# MCP960XL-L0X-RL0X_EVM_v1.net
KiCad netlist of a schematic drawn in EAGLE
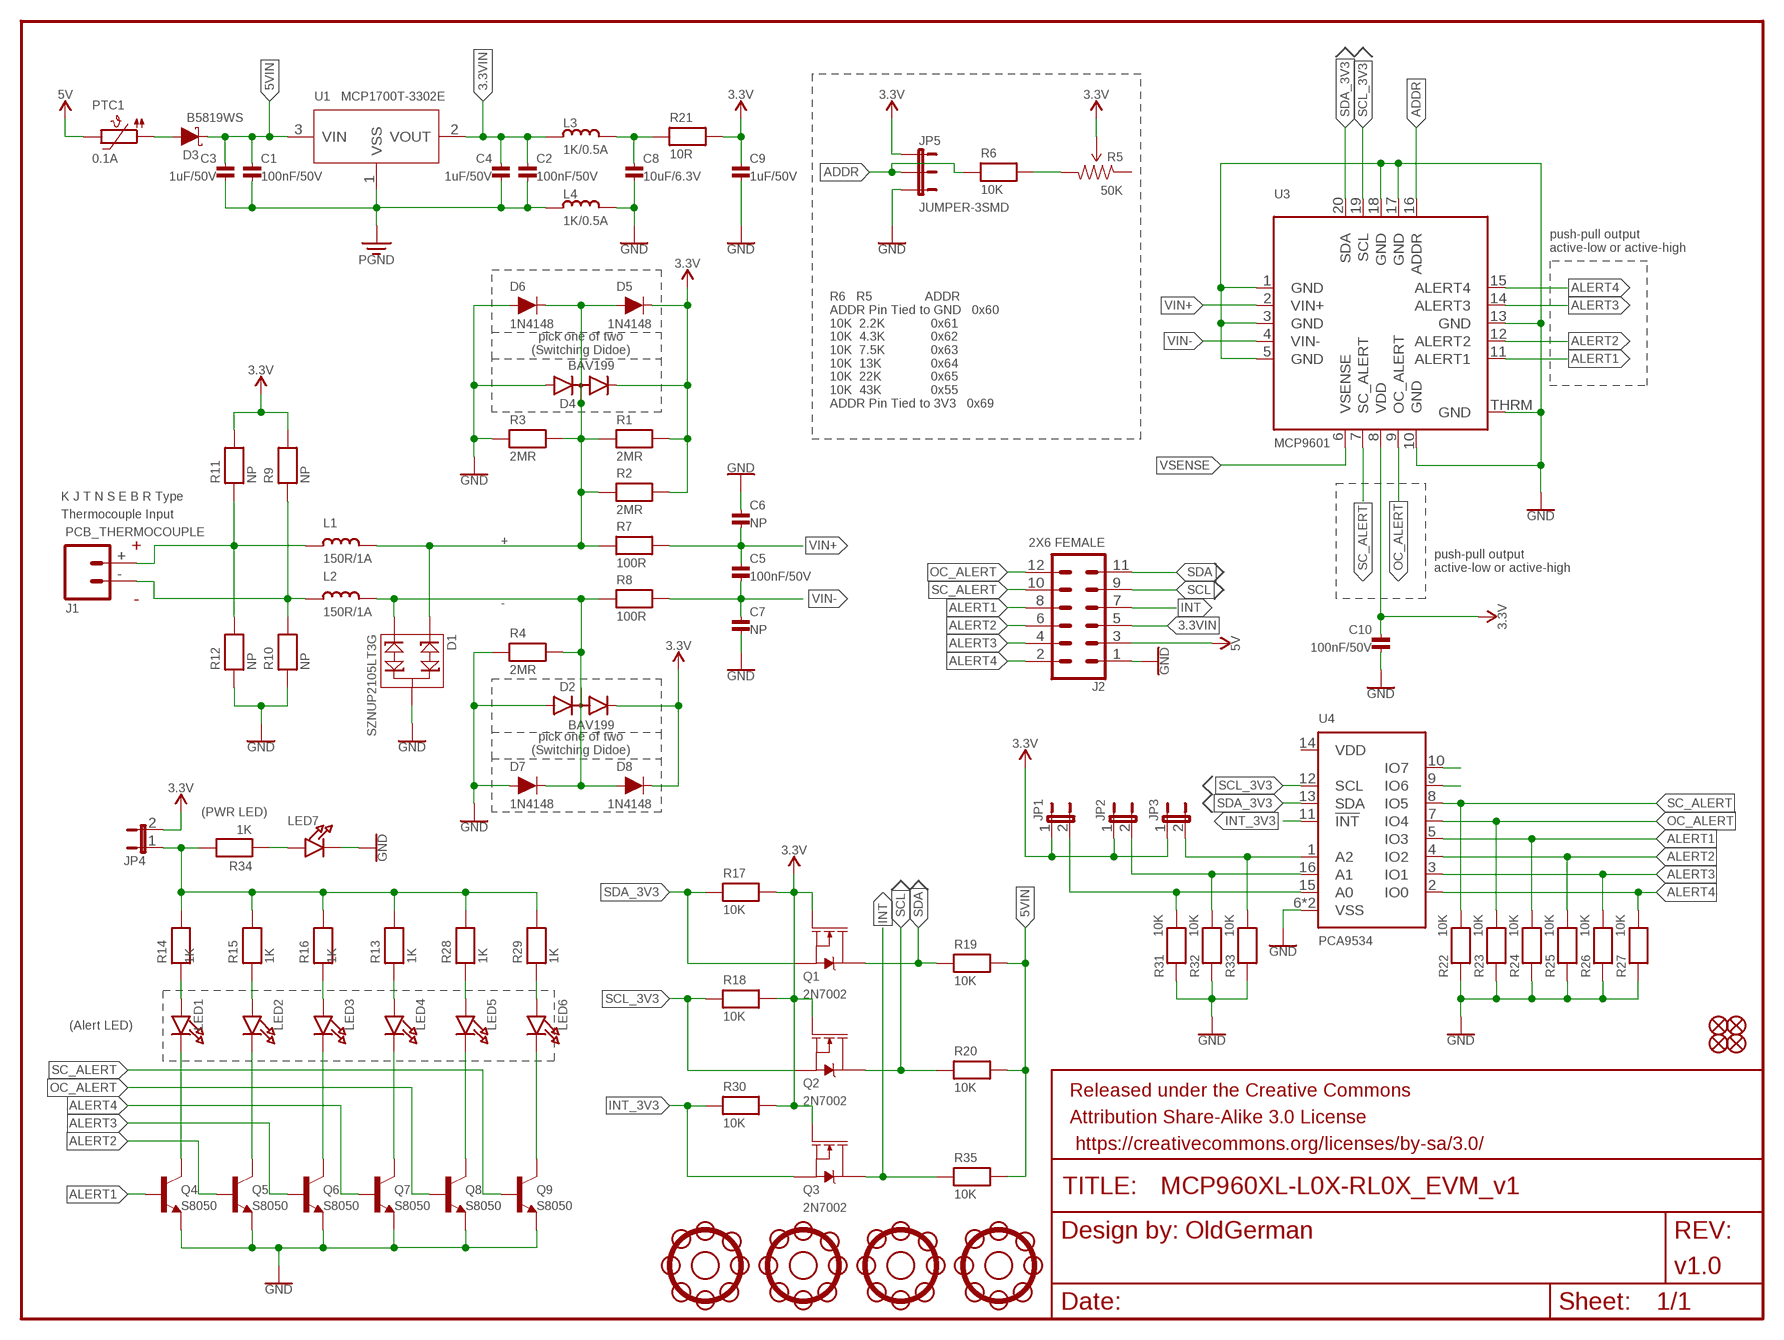
[diagram p0: schematic, sheet 1]

(export (version "E")
  (design (tool "Eeschema 10.0.6"))
  (components
    (comp (ref "C1")
      (value "100nF/50V")
      (footprint "eagle-import:0603")
      (libsource (lib "eagle-import") (part "CAP_CERAMIC0603"))
    )
    (comp (ref "C2")
      (value "100nF/50V")
      (footprint "eagle-import:0603")
      (libsource (lib "eagle-import") (part "CAP_CERAMIC0603"))
    )
    (comp (ref "C3")
      (value "1uF/50V")
      (footprint "eagle-import:0603")
      (libsource (lib "eagle-import") (part "CAP_CERAMIC0603"))
    )
    (comp (ref "C4")
      (value "1uF/50V")
      (footprint "eagle-import:0603")
      (libsource (lib "eagle-import") (part "CAP_CERAMIC0603"))
    )
    (comp (ref "C5")
      (value "100nF/50V")
      (footprint "eagle-import:0603")
      (libsource (lib "eagle-import") (part "CAP_CERAMIC0603"))
    )
    (comp (ref "C6")
      (value "NP")
      (footprint "eagle-import:0603")
      (libsource (lib "eagle-import") (part "CAP_CERAMIC0603"))
    )
    (comp (ref "C7")
      (value "NP")
      (footprint "eagle-import:0603")
      (libsource (lib "eagle-import") (part "CAP_CERAMIC0603"))
    )
    (comp (ref "C8")
      (value "10uF/6.3V")
      (footprint "eagle-import:0603")
      (libsource (lib "eagle-import") (part "CAP_CERAMIC0603"))
    )
    (comp (ref "C9")
      (value "1uF/50V")
      (footprint "eagle-import:0603")
      (libsource (lib "eagle-import") (part "CAP_CERAMIC0603"))
    )
    (comp (ref "C10")
      (value "100nF/50V")
      (footprint "eagle-import:0603")
      (libsource (lib "eagle-import") (part "CAP_CERAMIC0603"))
    )
    (comp (ref "D1")
      (value "SZNUP2105LT3G")
      (footprint "eagle-import:SOT23-3")
      (libsource (lib "eagle-import") (part "SZNUP2105LT3G"))
    )
    (comp (ref "D2")
      (value "BAV199")
      (footprint "eagle-import:SOT23-3")
      (libsource (lib "eagle-import") (part "BAV199"))
    )
    (comp (ref "D3")
      (value "B5819WS")
      (footprint "eagle-import:SOD-323")
      (libsource (lib "eagle-import") (part "DIODE_SCHOTTKYSOD323"))
    )
    (comp (ref "D4")
      (value "BAV199")
      (footprint "eagle-import:SOT23-3")
      (libsource (lib "eagle-import") (part "BAV199"))
    )
    (comp (ref "D5")
      (value "1N4148")
      (footprint "eagle-import:SOD-323")
      (libsource (lib "eagle-import") (part "DIODE"))
    )
    (comp (ref "D6")
      (value "1N4148")
      (footprint "eagle-import:SOD-323")
      (libsource (lib "eagle-import") (part "DIODE"))
    )
    (comp (ref "D7")
      (value "1N4148")
      (footprint "eagle-import:SOD-323")
      (libsource (lib "eagle-import") (part "DIODE"))
    )
    (comp (ref "D8")
      (value "1N4148")
      (footprint "eagle-import:SOD-323")
      (libsource (lib "eagle-import") (part "DIODE"))
    )
    (comp (ref "FID1")
      (value "FIDUCIAL1X2.5")
      (footprint "eagle-import:FIDUCIAL-1X2.5")
      (libsource (lib "eagle-import") (part "FIDUCIAL1X2.5"))
    )
    (comp (ref "FID2")
      (value "FIDUCIAL1X2.5")
      (footprint "eagle-import:FIDUCIAL-1X2.5")
      (libsource (lib "eagle-import") (part "FIDUCIAL1X2.5"))
    )
    (comp (ref "FID3")
      (value "FIDUCIAL1X2.5")
      (footprint "eagle-import:FIDUCIAL-1X2.5")
      (libsource (lib "eagle-import") (part "FIDUCIAL1X2.5"))
    )
    (comp (ref "FID4")
      (value "FIDUCIAL1X2.5")
      (footprint "eagle-import:FIDUCIAL-1X2.5")
      (libsource (lib "eagle-import") (part "FIDUCIAL1X2.5"))
    )
    (comp (ref "FRAME1")
      (value "FRAME-LETTER")
      (footprint "eagle-import:CREATIVE_COMMONS")
      (libsource (lib "eagle-import") (part "FRAME-LETTER"))
    )
    (comp (ref "J1")
      (value "PCB_THERMOCOUPLE")
      (footprint "eagle-import:PCC-SMP")
      (libsource (lib "eagle-import") (part "PCB_THERMOCOUPLE"))
    )
    (comp (ref "J2")
      (value "2X6 FEMALE")
      (footprint "eagle-import:2X6")
      (libsource (lib "eagle-import") (part "CONN_06X2PTH_FEMALE"))
    )
    (comp (ref "JP1")
      (value "JUMPER-2SMD-NC")
      (footprint "eagle-import:SJ_2S")
      (libsource (lib "eagle-import") (part "JUMPER-2SMD-NC"))
    )
    (comp (ref "JP2")
      (value "JUMPER-2SMD-NC")
      (footprint "eagle-import:SJ_2S")
      (libsource (lib "eagle-import") (part "JUMPER-2SMD-NC"))
    )
    (comp (ref "JP3")
      (value "JUMPER-2SMD-NC")
      (footprint "eagle-import:SJ_2S")
      (libsource (lib "eagle-import") (part "JUMPER-2SMD-NC"))
    )
    (comp (ref "JP4")
      (value "JUMPER-2SMD-NC")
      (footprint "eagle-import:SJ_2S")
      (libsource (lib "eagle-import") (part "JUMPER-2SMD-NC"))
    )
    (comp (ref "JP5")
      (value "JUMPER-3SMD")
      (footprint "eagle-import:SJ_3")
      (libsource (lib "eagle-import") (part "JUMPER-3SMD"))
    )
    (comp (ref "L1")
      (value "150R/1A")
      (footprint "eagle-import:0603")
      (libsource (lib "eagle-import") (part "INDUCTOR0603"))
    )
    (comp (ref "L2")
      (value "150R/1A")
      (footprint "eagle-import:0603")
      (libsource (lib "eagle-import") (part "INDUCTOR0603"))
    )
    (comp (ref "L3")
      (value "1K/0.5A")
      (footprint "eagle-import:0603")
      (libsource (lib "eagle-import") (part "INDUCTOR0603"))
    )
    (comp (ref "L4")
      (value "1K/0.5A")
      (footprint "eagle-import:0603")
      (libsource (lib "eagle-import") (part "INDUCTOR0603"))
    )
    (comp (ref "LED1")
      (value "LED0603")
      (footprint "eagle-import:CHIPLED_0603")
      (libsource (lib "eagle-import") (part "LED0603"))
    )
    (comp (ref "LED2")
      (value "LED0603")
      (footprint "eagle-import:CHIPLED_0603")
      (libsource (lib "eagle-import") (part "LED0603"))
    )
    (comp (ref "LED3")
      (value "LED0603")
      (footprint "eagle-import:CHIPLED_0603")
      (libsource (lib "eagle-import") (part "LED0603"))
    )
    (comp (ref "LED4")
      (value "LED0603")
      (footprint "eagle-import:CHIPLED_0603")
      (libsource (lib "eagle-import") (part "LED0603"))
    )
    (comp (ref "LED5")
      (value "LED0603")
      (footprint "eagle-import:CHIPLED_0603")
      (libsource (lib "eagle-import") (part "LED0603"))
    )
    (comp (ref "LED6")
      (value "LED0603")
      (footprint "eagle-import:CHIPLED_0603")
      (libsource (lib "eagle-import") (part "LED0603"))
    )
    (comp (ref "LED7")
      (value "LED0603")
      (footprint "eagle-import:CHIPLED_0603")
      (libsource (lib "eagle-import") (part "LED0603"))
    )
    (comp (ref "PTC1")
      (value "0.1A")
      (footprint "eagle-import:1206")
      (libsource (lib "eagle-import") (part "PTC1206"))
    )
    (comp (ref "Q1")
      (value "2N7002")
      (footprint "eagle-import:SOT23-3")
      (libsource (lib "eagle-import") (part "MOSFET-NCH-AO3404A"))
    )
    (comp (ref "Q2")
      (value "2N7002")
      (footprint "eagle-import:SOT23-3")
      (libsource (lib "eagle-import") (part "MOSFET-NCH-AO3404A"))
    )
    (comp (ref "Q3")
      (value "2N7002")
      (footprint "eagle-import:SOT23-3")
      (libsource (lib "eagle-import") (part "MOSFET-NCH-AO3404A"))
    )
    (comp (ref "Q4")
      (value "S8050")
      (footprint "eagle-import:SOT23-3")
      (libsource (lib "eagle-import") (part "TRANS_NPN-MMBT2222AL"))
    )
    (comp (ref "Q5")
      (value "S8050")
      (footprint "eagle-import:SOT23-3")
      (libsource (lib "eagle-import") (part "TRANS_NPN-MMBT2222AL"))
    )
    (comp (ref "Q6")
      (value "S8050")
      (footprint "eagle-import:SOT23-3")
      (libsource (lib "eagle-import") (part "TRANS_NPN-MMBT2222AL"))
    )
    (comp (ref "Q7")
      (value "S8050")
      (footprint "eagle-import:SOT23-3")
      (libsource (lib "eagle-import") (part "TRANS_NPN-MMBT2222AL"))
    )
    (comp (ref "Q8")
      (value "S8050")
      (footprint "eagle-import:SOT23-3")
      (libsource (lib "eagle-import") (part "TRANS_NPN-MMBT2222AL"))
    )
    (comp (ref "Q9")
      (value "S8050")
      (footprint "eagle-import:SOT23-3")
      (libsource (lib "eagle-import") (part "TRANS_NPN-MMBT2222AL"))
    )
    (comp (ref "R1")
      (value "2MR")
      (footprint "eagle-import:0603")
      (libsource (lib "eagle-import") (part "RESISTOR0603"))
    )
    (comp (ref "R2")
      (value "2MR")
      (footprint "eagle-import:0603")
      (libsource (lib "eagle-import") (part "RESISTOR0603"))
    )
    (comp (ref "R3")
      (value "2MR")
      (footprint "eagle-import:0603")
      (libsource (lib "eagle-import") (part "RESISTOR0603"))
    )
    (comp (ref "R4")
      (value "2MR")
      (footprint "eagle-import:0603")
      (libsource (lib "eagle-import") (part "RESISTOR0603"))
    )
    (comp (ref "R5")
      (value "50K")
      (footprint "eagle-import:TRIMPOT-3MM")
      (libsource (lib "eagle-import") (part "POT-SMD"))
    )
    (comp (ref "R6")
      (value "10K")
      (footprint "eagle-import:0603")
      (libsource (lib "eagle-import") (part "RESISTOR0603"))
    )
    (comp (ref "R7")
      (value "100R")
      (footprint "eagle-import:0603")
      (libsource (lib "eagle-import") (part "RESISTOR0603"))
    )
    (comp (ref "R8")
      (value "100R")
      (footprint "eagle-import:0603")
      (libsource (lib "eagle-import") (part "RESISTOR0603"))
    )
    (comp (ref "R9")
      (value "NP")
      (footprint "eagle-import:0603")
      (libsource (lib "eagle-import") (part "RESISTOR0603"))
    )
    (comp (ref "R10")
      (value "NP")
      (footprint "eagle-import:0603")
      (libsource (lib "eagle-import") (part "RESISTOR0603"))
    )
    (comp (ref "R11")
      (value "NP")
      (footprint "eagle-import:0603")
      (libsource (lib "eagle-import") (part "RESISTOR0603"))
    )
    (comp (ref "R12")
      (value "NP")
      (footprint "eagle-import:0603")
      (libsource (lib "eagle-import") (part "RESISTOR0603"))
    )
    (comp (ref "R13")
      (value "1K")
      (footprint "eagle-import:0603")
      (libsource (lib "eagle-import") (part "RESISTOR0603"))
    )
    (comp (ref "R14")
      (value "1K")
      (footprint "eagle-import:0603")
      (libsource (lib "eagle-import") (part "RESISTOR0603"))
    )
    (comp (ref "R15")
      (value "1K")
      (footprint "eagle-import:0603")
      (libsource (lib "eagle-import") (part "RESISTOR0603"))
    )
    (comp (ref "R16")
      (value "1K")
      (footprint "eagle-import:0603")
      (libsource (lib "eagle-import") (part "RESISTOR0603"))
    )
    (comp (ref "R17")
      (value "10K")
      (footprint "eagle-import:0603")
      (libsource (lib "eagle-import") (part "RESISTOR0603"))
    )
    (comp (ref "R18")
      (value "10K")
      (footprint "eagle-import:0603")
      (libsource (lib "eagle-import") (part "RESISTOR0603"))
    )
    (comp (ref "R19")
      (value "10K")
      (footprint "eagle-import:0603")
      (libsource (lib "eagle-import") (part "RESISTOR0603"))
    )
    (comp (ref "R20")
      (value "10K")
      (footprint "eagle-import:0603")
      (libsource (lib "eagle-import") (part "RESISTOR0603"))
    )
    (comp (ref "R21")
      (value "10R")
      (footprint "eagle-import:0603")
      (libsource (lib "eagle-import") (part "RESISTOR0603"))
    )
    (comp (ref "R22")
      (value "10K")
      (footprint "eagle-import:0603")
      (libsource (lib "eagle-import") (part "RESISTOR0603"))
    )
    (comp (ref "R23")
      (value "10K")
      (footprint "eagle-import:0603")
      (libsource (lib "eagle-import") (part "RESISTOR0603"))
    )
    (comp (ref "R24")
      (value "10K")
      (footprint "eagle-import:0603")
      (libsource (lib "eagle-import") (part "RESISTOR0603"))
    )
    (comp (ref "R25")
      (value "10K")
      (footprint "eagle-import:0603")
      (libsource (lib "eagle-import") (part "RESISTOR0603"))
    )
    (comp (ref "R26")
      (value "10K")
      (footprint "eagle-import:0603")
      (libsource (lib "eagle-import") (part "RESISTOR0603"))
    )
    (comp (ref "R27")
      (value "10K")
      (footprint "eagle-import:0603")
      (libsource (lib "eagle-import") (part "RESISTOR0603"))
    )
    (comp (ref "R28")
      (value "1K")
      (footprint "eagle-import:0603")
      (libsource (lib "eagle-import") (part "RESISTOR0603"))
    )
    (comp (ref "R29")
      (value "1K")
      (footprint "eagle-import:0603")
      (libsource (lib "eagle-import") (part "RESISTOR0603"))
    )
    (comp (ref "R30")
      (value "10K")
      (footprint "eagle-import:0603")
      (libsource (lib "eagle-import") (part "RESISTOR0603"))
    )
    (comp (ref "R31")
      (value "10K")
      (footprint "eagle-import:0603")
      (libsource (lib "eagle-import") (part "RESISTOR0603"))
    )
    (comp (ref "R32")
      (value "10K")
      (footprint "eagle-import:0603")
      (libsource (lib "eagle-import") (part "RESISTOR0603"))
    )
    (comp (ref "R33")
      (value "10K")
      (footprint "eagle-import:0603")
      (libsource (lib "eagle-import") (part "RESISTOR0603"))
    )
    (comp (ref "R34")
      (value "1K")
      (footprint "eagle-import:0603")
      (libsource (lib "eagle-import") (part "RESISTOR0603"))
    )
    (comp (ref "R35")
      (value "10K")
      (footprint "eagle-import:0603")
      (libsource (lib "eagle-import") (part "RESISTOR0603"))
    )
    (comp (ref "U$1")
      (value "SUN_HOLE_M3")
      (footprint "eagle-import:SUN_HOLE_M3")
      (libsource (lib "eagle-import") (part "SUN_HOLE_M3"))
    )
    (comp (ref "U$3")
      (value "SUN_HOLE_M3")
      (footprint "eagle-import:SUN_HOLE_M3")
      (libsource (lib "eagle-import") (part "SUN_HOLE_M3"))
    )
    (comp (ref "U$4")
      (value "SUN_HOLE_M3")
      (footprint "eagle-import:SUN_HOLE_M3")
      (libsource (lib "eagle-import") (part "SUN_HOLE_M3"))
    )
    (comp (ref "U$6")
      (value "SUN_HOLE_M3")
      (footprint "eagle-import:SUN_HOLE_M3")
      (libsource (lib "eagle-import") (part "SUN_HOLE_M3"))
    )
    (comp (ref "U1")
      (value "MCP1700T-3302E")
      (footprint "eagle-import:SOT23-3")
      (libsource (lib "eagle-import") (part "LDO_3PIN"))
    )
    (comp (ref "U3")
      (value "MCP9601")
      (footprint "eagle-import:VQFN20_5MM")
      (libsource (lib "eagle-import") (part "MCP9601"))
    )
    (comp (ref "U4")
      (value "PCA9534")
      (footprint "eagle-import:HVQFN16_4X4_0.65MM")
      (libsource (lib "eagle-import") (part "PCA9534"))
    )
  )
  (nets
    (net (code "1") (name "/VDD") (class "Default")
      (node (ref "U4") (pin "14") (pinfunction "VDD_14") (pintype "power_in"))
    )
    (net (code "2") (name "3.3V") (class "Default")
      (node (ref "C10") (pin "1") (pinfunction "P$1_1") (pintype "passive"))
      (node (ref "C9") (pin "1") (pinfunction "P$1_1") (pintype "passive"))
      (node (ref "D2") (pin "3") (pinfunction "C_3") (pintype "passive"))
      (node (ref "D4") (pin "3") (pinfunction "C_3") (pintype "passive"))
      (node (ref "D5") (pin "C") (pinfunction "C_C") (pintype "passive"))
      (node (ref "D8") (pin "C") (pinfunction "C_C") (pintype "passive"))
      (node (ref "JP1") (pin "1") (pinfunction "1_1") (pintype "passive"))
      (node (ref "JP2") (pin "1") (pinfunction "1_1") (pintype "passive"))
      (node (ref "JP3") (pin "1") (pinfunction "1_1") (pintype "passive"))
      (node (ref "JP4") (pin "2") (pinfunction "2_2") (pintype "passive"))
      (node (ref "JP5") (pin "1") (pinfunction "1_1") (pintype "passive"))
      (node (ref "Q1") (pin "1") (pinfunction "G_1") (pintype "bidirectional"))
      (node (ref "Q2") (pin "1") (pinfunction "G_1") (pintype "bidirectional"))
      (node (ref "Q3") (pin "1") (pinfunction "G_1") (pintype "bidirectional"))
      (node (ref "R1") (pin "2") (pinfunction "2_2") (pintype "passive"))
      (node (ref "R11") (pin "2") (pinfunction "2_2") (pintype "passive"))
      (node (ref "R17") (pin "2") (pinfunction "2_2") (pintype "passive"))
      (node (ref "R18") (pin "2") (pinfunction "2_2") (pintype "passive"))
      (node (ref "R2") (pin "2") (pinfunction "2_2") (pintype "passive"))
      (node (ref "R21") (pin "2") (pinfunction "2_2") (pintype "passive"))
      (node (ref "R30") (pin "2") (pinfunction "2_2") (pintype "passive"))
      (node (ref "R5") (pin "2") (pinfunction "WIPER_2") (pintype "passive"))
      (node (ref "R9") (pin "2") (pinfunction "2_2") (pintype "passive"))
      (node (ref "U3") (pin "8") (pinfunction "VDD_8") (pintype "bidirectional"))
    )
    (net (code "3") (name "3.3VIN") (class "Default")
      (node (ref "C2") (pin "1") (pinfunction "P$1_1") (pintype "passive"))
      (node (ref "C4") (pin "1") (pinfunction "P$1_1") (pintype "passive"))
      (node (ref "J2") (pin "5") (pinfunction "5_5") (pintype "passive"))
      (node (ref "L3") (pin "1") (pinfunction "1_1") (pintype "passive"))
      (node (ref "U1") (pin "2") (pinfunction "VOUT_2") (pintype "bidirectional"))
    )
    (net (code "4") (name "5V") (class "Default")
      (node (ref "J2") (pin "3") (pinfunction "3_3") (pintype "passive"))
      (node (ref "PTC1") (pin "2") (pinfunction "2_2") (pintype "passive"))
    )
    (net (code "5") (name "5VIN") (class "Default")
      (node (ref "C1") (pin "1") (pinfunction "P$1_1") (pintype "passive"))
      (node (ref "C3") (pin "1") (pinfunction "P$1_1") (pintype "passive"))
      (node (ref "D3") (pin "C") (pinfunction "C_C") (pintype "passive"))
      (node (ref "R19") (pin "2") (pinfunction "2_2") (pintype "passive"))
      (node (ref "R20") (pin "2") (pinfunction "2_2") (pintype "passive"))
      (node (ref "R35") (pin "2") (pinfunction "2_2") (pintype "passive"))
      (node (ref "U1") (pin "3") (pinfunction "VIN_3") (pintype "bidirectional"))
    )
    (net (code "6") (name "ADDR") (class "Default")
      (node (ref "JP5") (pin "2") (pinfunction "2_2") (pintype "passive"))
      (node (ref "R6") (pin "1") (pinfunction "1_1") (pintype "passive"))
      (node (ref "U3") (pin "16") (pinfunction "ADDR_16") (pintype "bidirectional"))
    )
    (net (code "7") (name "ALERT1") (class "Default")
      (node (ref "J2") (pin "8") (pinfunction "8_8") (pintype "passive"))
      (node (ref "Q4") (pin "1") (pinfunction "B_1") (pintype "passive"))
      (node (ref "R24") (pin "2") (pinfunction "2_2") (pintype "passive"))
      (node (ref "U3") (pin "11") (pinfunction "ALERT1_11") (pintype "bidirectional"))
      (node (ref "U4") (pin "5") (pinfunction "IO3_5") (pintype "bidirectional"))
    )
    (net (code "8") (name "ALERT2") (class "Default")
      (node (ref "J2") (pin "6") (pinfunction "6_6") (pintype "passive"))
      (node (ref "Q5") (pin "1") (pinfunction "B_1") (pintype "passive"))
      (node (ref "R25") (pin "2") (pinfunction "2_2") (pintype "passive"))
      (node (ref "U3") (pin "12") (pinfunction "ALERT2_12") (pintype "bidirectional"))
      (node (ref "U4") (pin "4") (pinfunction "IO2_4") (pintype "bidirectional"))
    )
    (net (code "9") (name "ALERT3") (class "Default")
      (node (ref "J2") (pin "4") (pinfunction "4_4") (pintype "passive"))
      (node (ref "Q6") (pin "1") (pinfunction "B_1") (pintype "passive"))
      (node (ref "R26") (pin "2") (pinfunction "2_2") (pintype "passive"))
      (node (ref "U3") (pin "14") (pinfunction "ALERT3_14") (pintype "bidirectional"))
      (node (ref "U4") (pin "3") (pinfunction "IO1_3") (pintype "bidirectional"))
    )
    (net (code "10") (name "ALERT4") (class "Default")
      (node (ref "J2") (pin "2") (pinfunction "2_2") (pintype "passive"))
      (node (ref "Q7") (pin "1") (pinfunction "B_1") (pintype "passive"))
      (node (ref "R27") (pin "2") (pinfunction "2_2") (pintype "passive"))
      (node (ref "U3") (pin "15") (pinfunction "ALERT4_15") (pintype "bidirectional"))
      (node (ref "U4") (pin "2") (pinfunction "IO0_2") (pintype "bidirectional"))
    )
    (net (code "11") (name "GND") (class "Default")
      (node (ref "C10") (pin "2") (pinfunction "P$2_2") (pintype "passive"))
      (node (ref "C6") (pin "1") (pinfunction "P$1_1") (pintype "passive"))
      (node (ref "C7") (pin "2") (pinfunction "P$2_2") (pintype "passive"))
      (node (ref "C8") (pin "2") (pinfunction "P$2_2") (pintype "passive"))
      (node (ref "C9") (pin "2") (pinfunction "P$2_2") (pintype "passive"))
      (node (ref "D1") (pin "3") (pinfunction "3_3") (pintype "bidirectional"))
      (node (ref "D2") (pin "1") (pinfunction "A_1") (pintype "passive"))
      (node (ref "D4") (pin "1") (pinfunction "A_1") (pintype "passive"))
      (node (ref "D6") (pin "A") (pinfunction "A_A") (pintype "passive"))
      (node (ref "D7") (pin "A") (pinfunction "A_A") (pintype "passive"))
      (node (ref "J2") (pin "1") (pinfunction "1_1") (pintype "passive"))
      (node (ref "JP5") (pin "3") (pinfunction "3_3") (pintype "passive"))
      (node (ref "L4") (pin "2") (pinfunction "2_2") (pintype "passive"))
      (node (ref "LED7") (pin "C") (pinfunction "C_C") (pintype "passive"))
      (node (ref "Q4") (pin "2") (pinfunction "E_2") (pintype "passive"))
      (node (ref "Q5") (pin "2") (pinfunction "E_2") (pintype "passive"))
      (node (ref "Q6") (pin "2") (pinfunction "E_2") (pintype "passive"))
      (node (ref "Q7") (pin "2") (pinfunction "E_2") (pintype "passive"))
      (node (ref "Q8") (pin "2") (pinfunction "E_2") (pintype "passive"))
      (node (ref "Q9") (pin "2") (pinfunction "E_2") (pintype "passive"))
      (node (ref "R10") (pin "1") (pinfunction "1_1") (pintype "passive"))
      (node (ref "R12") (pin "1") (pinfunction "1_1") (pintype "passive"))
      (node (ref "R22") (pin "1") (pinfunction "1_1") (pintype "passive"))
      (node (ref "R23") (pin "1") (pinfunction "1_1") (pintype "passive"))
      (node (ref "R24") (pin "1") (pinfunction "1_1") (pintype "passive"))
      (node (ref "R25") (pin "1") (pinfunction "1_1") (pintype "passive"))
      (node (ref "R26") (pin "1") (pinfunction "1_1") (pintype "passive"))
      (node (ref "R27") (pin "1") (pinfunction "1_1") (pintype "passive"))
      (node (ref "R3") (pin "1") (pinfunction "1_1") (pintype "passive"))
      (node (ref "R31") (pin "1") (pinfunction "1_1") (pintype "passive"))
      (node (ref "R32") (pin "1") (pinfunction "1_1") (pintype "passive"))
      (node (ref "R33") (pin "1") (pinfunction "1_1") (pintype "passive"))
      (node (ref "R4") (pin "1") (pinfunction "1_1") (pintype "passive"))
      (node (ref "U3") (pin "1") (pinfunction "GND_1") (pintype "bidirectional"))
      (node (ref "U3") (pin "10") (pinfunction "GND_10") (pintype "bidirectional"))
      (node (ref "U3") (pin "13") (pinfunction "GND_13") (pintype "bidirectional"))
      (node (ref "U3") (pin "17") (pinfunction "GND_17") (pintype "bidirectional"))
      (node (ref "U3") (pin "18") (pinfunction "GND_18") (pintype "bidirectional"))
      (node (ref "U3") (pin "3") (pinfunction "GND_3") (pintype "bidirectional"))
      (node (ref "U3") (pin "5") (pinfunction "GND_5") (pintype "bidirectional"))
      (node (ref "U3") (pin "THRM") (pinfunction "GND_THRM") (pintype "bidirectional"))
      (node (ref "U4") (pin "6") (pinfunction "VSS_6") (pintype "power_in"))
      (node (ref "U4") (pin "PAD") (pinfunction "VSS_PAD") (pintype "power_in"))
    )
    (net (code "12") (name "INT") (class "Default")
      (node (ref "J2") (pin "7") (pinfunction "7_7") (pintype "passive"))
      (node (ref "Q3") (pin "3") (pinfunction "D_3") (pintype "bidirectional"))
      (node (ref "R35") (pin "1") (pinfunction "1_1") (pintype "passive"))
    )
    (net (code "13") (name "INT_3V3") (class "Default")
      (node (ref "Q3") (pin "2") (pinfunction "S_2") (pintype "bidirectional"))
      (node (ref "R30") (pin "1") (pinfunction "1_1") (pintype "passive"))
      (node (ref "U4") (pin "11") (pinfunction "~{INT}_11") (pintype "open_collector"))
    )
    (net (code "14") (name "Net-(C8-P$1)") (class "Default")
      (node (ref "C8") (pin "1") (pinfunction "P$1_1") (pintype "passive"))
      (node (ref "L3") (pin "2") (pinfunction "2_2") (pintype "passive"))
      (node (ref "R21") (pin "1") (pinfunction "1_1") (pintype "passive"))
    )
    (net (code "15") (name "Net-(D2-AC)") (class "Default")
      (node (ref "D1") (pin "2") (pinfunction "2_2") (pintype "power_in"))
      (node (ref "D2") (pin "2") (pinfunction "AC_2") (pintype "passive"))
      (node (ref "D7") (pin "C") (pinfunction "C_C") (pintype "passive"))
      (node (ref "D8") (pin "A") (pinfunction "A_A") (pintype "passive"))
      (node (ref "L2") (pin "2") (pinfunction "2_2") (pintype "passive"))
      (node (ref "R4") (pin "2") (pinfunction "2_2") (pintype "passive"))
      (node (ref "R8") (pin "1") (pinfunction "1_1") (pintype "passive"))
    )
    (net (code "16") (name "Net-(D3-PadA)") (class "Default")
      (node (ref "D3") (pin "A") (pinfunction "A_A") (pintype "passive"))
      (node (ref "PTC1") (pin "1") (pinfunction "1_1") (pintype "passive"))
    )
    (net (code "17") (name "Net-(D4-AC)") (class "Default")
      (node (ref "D1") (pin "1") (pinfunction "1_1") (pintype "power_in"))
      (node (ref "D4") (pin "2") (pinfunction "AC_2") (pintype "passive"))
      (node (ref "D5") (pin "A") (pinfunction "A_A") (pintype "passive"))
      (node (ref "D6") (pin "C") (pinfunction "C_C") (pintype "passive"))
      (node (ref "L1") (pin "2") (pinfunction "2_2") (pintype "passive"))
      (node (ref "R1") (pin "1") (pinfunction "1_1") (pintype "passive"))
      (node (ref "R2") (pin "1") (pinfunction "1_1") (pintype "passive"))
      (node (ref "R3") (pin "2") (pinfunction "2_2") (pintype "passive"))
      (node (ref "R7") (pin "1") (pinfunction "1_1") (pintype "passive"))
    )
    (net (code "18") (name "Net-(J1-Pad+)") (class "Default")
      (node (ref "J1") (pin "+") (pinfunction "+_+") (pintype "passive"))
      (node (ref "L1") (pin "1") (pinfunction "1_1") (pintype "passive"))
      (node (ref "R11") (pin "1") (pinfunction "1_1") (pintype "passive"))
      (node (ref "R12") (pin "2") (pinfunction "2_2") (pintype "passive"))
    )
    (net (code "19") (name "Net-(J1-Pad-)") (class "Default")
      (node (ref "J1") (pin "-") (pinfunction "-_-") (pintype "passive"))
      (node (ref "L2") (pin "1") (pinfunction "1_1") (pintype "passive"))
      (node (ref "R10") (pin "2") (pinfunction "2_2") (pintype "passive"))
      (node (ref "R9") (pin "1") (pinfunction "1_1") (pintype "passive"))
    )
    (net (code "20") (name "Net-(JP4-Pad1)") (class "Default")
      (node (ref "JP4") (pin "1") (pinfunction "1_1") (pintype "passive"))
      (node (ref "R13") (pin "2") (pinfunction "2_2") (pintype "passive"))
      (node (ref "R14") (pin "2") (pinfunction "2_2") (pintype "passive"))
      (node (ref "R15") (pin "2") (pinfunction "2_2") (pintype "passive"))
      (node (ref "R16") (pin "2") (pinfunction "2_2") (pintype "passive"))
      (node (ref "R28") (pin "2") (pinfunction "2_2") (pintype "passive"))
      (node (ref "R29") (pin "2") (pinfunction "2_2") (pintype "passive"))
      (node (ref "R34") (pin "2") (pinfunction "2_2") (pintype "passive"))
    )
    (net (code "21") (name "Net-(LED1-PadA)") (class "Default")
      (node (ref "LED1") (pin "A") (pinfunction "A_A") (pintype "passive"))
      (node (ref "R14") (pin "1") (pinfunction "1_1") (pintype "passive"))
    )
    (net (code "22") (name "Net-(LED2-PadA)") (class "Default")
      (node (ref "LED2") (pin "A") (pinfunction "A_A") (pintype "passive"))
      (node (ref "R15") (pin "1") (pinfunction "1_1") (pintype "passive"))
    )
    (net (code "23") (name "Net-(LED3-PadA)") (class "Default")
      (node (ref "LED3") (pin "A") (pinfunction "A_A") (pintype "passive"))
      (node (ref "R16") (pin "1") (pinfunction "1_1") (pintype "passive"))
    )
    (net (code "24") (name "Net-(LED4-PadA)") (class "Default")
      (node (ref "LED4") (pin "A") (pinfunction "A_A") (pintype "passive"))
      (node (ref "R13") (pin "1") (pinfunction "1_1") (pintype "passive"))
    )
    (net (code "25") (name "Net-(LED5-PadA)") (class "Default")
      (node (ref "LED5") (pin "A") (pinfunction "A_A") (pintype "passive"))
      (node (ref "R28") (pin "1") (pinfunction "1_1") (pintype "passive"))
    )
    (net (code "26") (name "Net-(LED6-PadA)") (class "Default")
      (node (ref "LED6") (pin "A") (pinfunction "A_A") (pintype "passive"))
      (node (ref "R29") (pin "1") (pinfunction "1_1") (pintype "passive"))
    )
    (net (code "27") (name "Net-(LED7-PadA)") (class "Default")
      (node (ref "LED7") (pin "A") (pinfunction "A_A") (pintype "passive"))
      (node (ref "R34") (pin "1") (pinfunction "1_1") (pintype "passive"))
    )
    (net (code "28") (name "Net-(Q4-C)") (class "Default")
      (node (ref "LED1") (pin "C") (pinfunction "C_C") (pintype "passive"))
      (node (ref "Q4") (pin "3") (pinfunction "C_3") (pintype "passive"))
    )
    (net (code "29") (name "Net-(Q5-C)") (class "Default")
      (node (ref "LED2") (pin "C") (pinfunction "C_C") (pintype "passive"))
      (node (ref "Q5") (pin "3") (pinfunction "C_3") (pintype "passive"))
    )
    (net (code "30") (name "Net-(Q6-C)") (class "Default")
      (node (ref "LED3") (pin "C") (pinfunction "C_C") (pintype "passive"))
      (node (ref "Q6") (pin "3") (pinfunction "C_3") (pintype "passive"))
    )
    (net (code "31") (name "Net-(Q7-C)") (class "Default")
      (node (ref "LED4") (pin "C") (pinfunction "C_C") (pintype "passive"))
      (node (ref "Q7") (pin "3") (pinfunction "C_3") (pintype "passive"))
    )
    (net (code "32") (name "Net-(Q8-C)") (class "Default")
      (node (ref "LED5") (pin "C") (pinfunction "C_C") (pintype "passive"))
      (node (ref "Q8") (pin "3") (pinfunction "C_3") (pintype "passive"))
    )
    (net (code "33") (name "Net-(Q9-C)") (class "Default")
      (node (ref "LED6") (pin "C") (pinfunction "C_C") (pintype "passive"))
      (node (ref "Q9") (pin "3") (pinfunction "C_3") (pintype "passive"))
    )
    (net (code "34") (name "Net-(R5-CW)") (class "Default")
      (node (ref "R5") (pin "1") (pinfunction "CW_1") (pintype "passive"))
      (node (ref "R6") (pin "2") (pinfunction "2_2") (pintype "passive"))
    )
    (net (code "35") (name "Net-(U4-A0)") (class "Default")
      (node (ref "JP1") (pin "2") (pinfunction "2_2") (pintype "passive"))
      (node (ref "R31") (pin "2") (pinfunction "2_2") (pintype "passive"))
      (node (ref "U4") (pin "15") (pinfunction "A0_15") (pintype "input"))
    )
    (net (code "36") (name "Net-(U4-A1)") (class "Default")
      (node (ref "JP2") (pin "2") (pinfunction "2_2") (pintype "passive"))
      (node (ref "R32") (pin "2") (pinfunction "2_2") (pintype "passive"))
      (node (ref "U4") (pin "16") (pinfunction "A1_16") (pintype "input"))
    )
    (net (code "37") (name "Net-(U4-A2)") (class "Default")
      (node (ref "JP3") (pin "2") (pinfunction "2_2") (pintype "passive"))
      (node (ref "R33") (pin "2") (pinfunction "2_2") (pintype "passive"))
      (node (ref "U4") (pin "1") (pinfunction "A2_1") (pintype "input"))
    )
    (net (code "38") (name "OC_ALERT") (class "Default")
      (node (ref "J2") (pin "12") (pinfunction "12_12") (pintype "passive"))
      (node (ref "Q8") (pin "1") (pinfunction "B_1") (pintype "passive"))
      (node (ref "R23") (pin "2") (pinfunction "2_2") (pintype "passive"))
      (node (ref "U3") (pin "9") (pinfunction "OC_ALERT_9") (pintype "bidirectional"))
      (node (ref "U4") (pin "7") (pinfunction "IO4_7") (pintype "bidirectional"))
    )
    (net (code "39") (name "PGND") (class "Default")
      (node (ref "C1") (pin "2") (pinfunction "P$2_2") (pintype "passive"))
      (node (ref "C2") (pin "2") (pinfunction "P$2_2") (pintype "passive"))
      (node (ref "C3") (pin "2") (pinfunction "P$2_2") (pintype "passive"))
      (node (ref "C4") (pin "2") (pinfunction "P$2_2") (pintype "passive"))
      (node (ref "L4") (pin "1") (pinfunction "1_1") (pintype "passive"))
      (node (ref "U1") (pin "1") (pinfunction "VSS_1") (pintype "bidirectional"))
    )
    (net (code "40") (name "SCL") (class "Default")
      (node (ref "J2") (pin "9") (pinfunction "9_9") (pintype "passive"))
      (node (ref "Q2") (pin "3") (pinfunction "D_3") (pintype "bidirectional"))
      (node (ref "R20") (pin "1") (pinfunction "1_1") (pintype "passive"))
    )
    (net (code "41") (name "SCL_3V3") (class "Default")
      (node (ref "Q2") (pin "2") (pinfunction "S_2") (pintype "bidirectional"))
      (node (ref "R18") (pin "1") (pinfunction "1_1") (pintype "passive"))
      (node (ref "U3") (pin "19") (pinfunction "SCL_19") (pintype "bidirectional"))
      (node (ref "U4") (pin "12") (pinfunction "SCL_12") (pintype "input"))
    )
    (net (code "42") (name "SC_ALERT") (class "Default")
      (node (ref "J2") (pin "10") (pinfunction "10_10") (pintype "passive"))
      (node (ref "Q9") (pin "1") (pinfunction "B_1") (pintype "passive"))
      (node (ref "R22") (pin "2") (pinfunction "2_2") (pintype "passive"))
      (node (ref "U3") (pin "7") (pinfunction "SC_ALERT_7") (pintype "bidirectional"))
      (node (ref "U4") (pin "8") (pinfunction "IO5_8") (pintype "bidirectional"))
    )
    (net (code "43") (name "SDA") (class "Default")
      (node (ref "J2") (pin "11") (pinfunction "11_11") (pintype "passive"))
      (node (ref "Q1") (pin "3") (pinfunction "D_3") (pintype "bidirectional"))
      (node (ref "R19") (pin "1") (pinfunction "1_1") (pintype "passive"))
    )
    (net (code "44") (name "SDA_3V3") (class "Default")
      (node (ref "Q1") (pin "2") (pinfunction "S_2") (pintype "bidirectional"))
      (node (ref "R17") (pin "1") (pinfunction "1_1") (pintype "passive"))
      (node (ref "U3") (pin "20") (pinfunction "SDA_20") (pintype "bidirectional"))
      (node (ref "U4") (pin "13") (pinfunction "SDA_13") (pintype "bidirectional"))
    )
    (net (code "45") (name "VIN+") (class "Default")
      (node (ref "C5") (pin "1") (pinfunction "P$1_1") (pintype "passive"))
      (node (ref "C6") (pin "2") (pinfunction "P$2_2") (pintype "passive"))
      (node (ref "R7") (pin "2") (pinfunction "2_2") (pintype "passive"))
      (node (ref "U3") (pin "2") (pinfunction "VIN+_2") (pintype "bidirectional"))
    )
    (net (code "46") (name "VIN-") (class "Default")
      (node (ref "C5") (pin "2") (pinfunction "P$2_2") (pintype "passive"))
      (node (ref "C7") (pin "1") (pinfunction "P$1_1") (pintype "passive"))
      (node (ref "R8") (pin "2") (pinfunction "2_2") (pintype "passive"))
      (node (ref "U3") (pin "4") (pinfunction "VIN-_4") (pintype "bidirectional"))
    )
    (net (code "47") (name "VSENSE") (class "Default")
      (node (ref "U3") (pin "6") (pinfunction "VSENSE_6") (pintype "bidirectional"))
    )
    (net (code "48") (name "unconnected-(R5-CCW-Pad3)") (class "Default")
      (node (ref "R5") (pin "3") (pinfunction "CCW_3") (pintype "passive"))
    )
    (net (code "49") (name "unconnected-(U4-IO6-Pad9)") (class "Default")
      (node (ref "U4") (pin "9") (pinfunction "IO6_9") (pintype "bidirectional"))
    )
    (net (code "50") (name "unconnected-(U4-IO7-Pad10)") (class "Default")
      (node (ref "U4") (pin "10") (pinfunction "IO7_10") (pintype "bidirectional"))
    )
  )
)
